# Battery_Charger.net
KiCad netlist of a schematic drawn in EAGLE
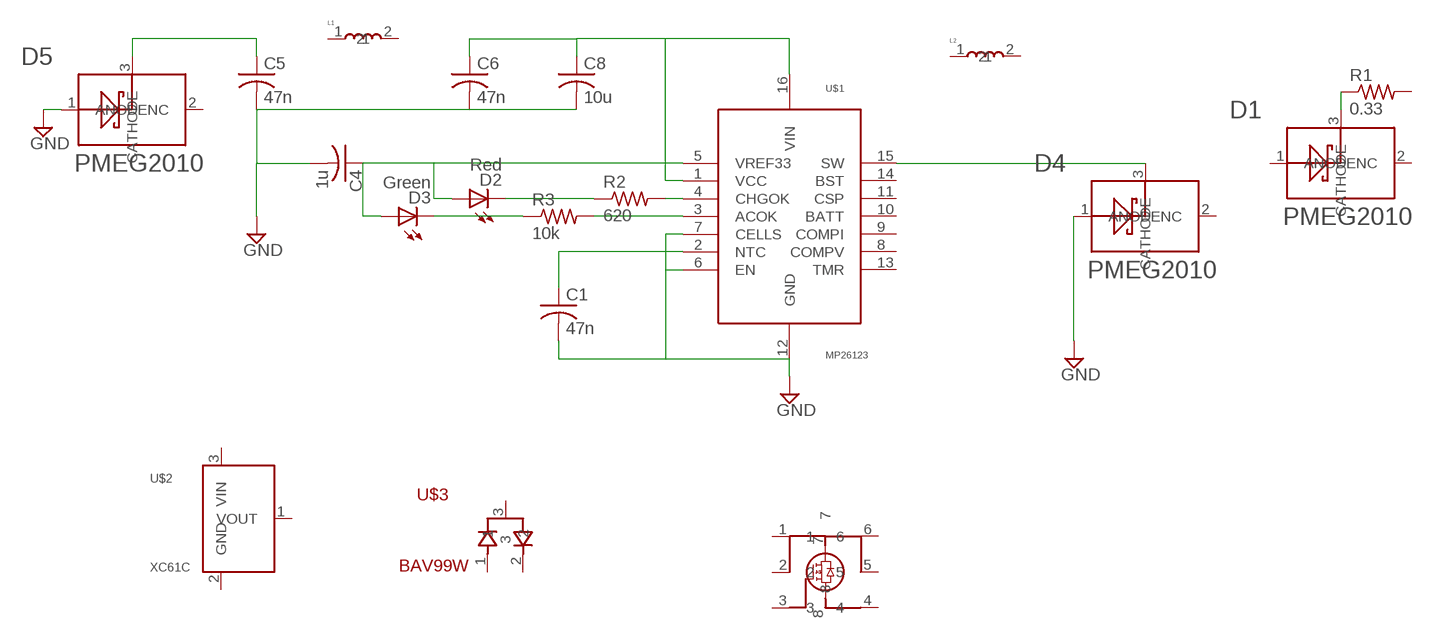
[diagram p0: schematic, sheet 1]

(export (version "E")
  (design (tool "Eeschema 10.0.6"))
  (components
    (comp (ref "C1")
      (value "47n")
      (footprint "eagle-import:C0805")
      (libsource (lib "eagle-import") (part "C-USC0805"))
    )
    (comp (ref "C4")
      (value "1u")
      (footprint "eagle-import:C0805")
      (libsource (lib "eagle-import") (part "C-USC0805"))
    )
    (comp (ref "C5")
      (value "47n")
      (footprint "eagle-import:C0805")
      (libsource (lib "eagle-import") (part "C-USC0805"))
    )
    (comp (ref "C6")
      (value "47n")
      (footprint "eagle-import:C0805")
      (libsource (lib "eagle-import") (part "C-USC0805"))
    )
    (comp (ref "C8")
      (value "10u")
      (footprint "eagle-import:C0805")
      (libsource (lib "eagle-import") (part "C-USC0805"))
    )
    (comp (ref "D1")
      (value "DIODE-PMEG2010")
      (footprint "eagle-import:DIODE-SOT23")
      (libsource (lib "eagle-import") (part "DIODE-PMEG2010"))
    )
    (comp (ref "D2")
      (value "Red")
      (footprint "eagle-import:LED3MM")
      (libsource (lib "eagle-import") (part "LED3MM"))
    )
    (comp (ref "D3")
      (value "Green")
      (footprint "eagle-import:LED3MM")
      (libsource (lib "eagle-import") (part "LED3MM"))
    )
    (comp (ref "D4")
      (value "DIODE-PMEG2010")
      (footprint "eagle-import:DIODE-SOT23")
      (libsource (lib "eagle-import") (part "DIODE-PMEG2010"))
    )
    (comp (ref "D5")
      (value "DIODE-PMEG2010")
      (footprint "eagle-import:DIODE-SOT23")
      (libsource (lib "eagle-import") (part "DIODE-PMEG2010"))
    )
    (comp (ref "L1")
      (value "L-SMD-2")
      (footprint "eagle-import:SMD-2")
      (libsource (lib "eagle-import") (part "L-SMD-2"))
    )
    (comp (ref "L2")
      (value "L-SMD-2")
      (footprint "eagle-import:SMD-2")
      (libsource (lib "eagle-import") (part "L-SMD-2"))
    )
    (comp (ref "Q1")
      (value "MOSFET-IRFHS8242")
      (footprint "eagle-import:PQFN2X2")
      (libsource (lib "eagle-import") (part "MOSFET-IRFHS8242"))
    )
    (comp (ref "R1")
      (value "0.33")
      (footprint "eagle-import:R2512")
      (libsource (lib "eagle-import") (part "R-US_R2512"))
    )
    (comp (ref "R2")
      (value "620")
      (footprint "eagle-import:R0805")
      (libsource (lib "eagle-import") (part "R-US_R0805"))
    )
    (comp (ref "R3")
      (value "10k")
      (footprint "eagle-import:R0805")
      (libsource (lib "eagle-import") (part "R-US_R0805"))
    )
    (comp (ref "U$1")
      (value "IC-MP26123")
      (footprint "eagle-import:QFN16-4MM")
      (libsource (lib "eagle-import") (part "IC-MP26123"))
    )
    (comp (ref "U$2")
      (value "IC-XC61C")
      (footprint "eagle-import:SOT23")
      (libsource (lib "eagle-import") (part "IC-XC61C"))
    )
    (comp (ref "U$3")
      (value "DIODE-BAV99W")
      (footprint "eagle-import:SOT323")
      (libsource (lib "eagle-import") (part "DIODE-BAV99W"))
    )
  )
  (nets
    (net (code "1") (name "/1") (class "Default")
      (node (ref "Q1") (pin "1") (pinfunction "1_1") (pintype "power_in"))
    )
    (net (code "2") (name "/2") (class "Default")
      (node (ref "Q1") (pin "2") (pinfunction "2_2") (pintype "power_in"))
    )
    (net (code "3") (name "/4") (class "Default")
      (node (ref "Q1") (pin "4") (pinfunction "4_4") (pintype "power_in"))
    )
    (net (code "4") (name "/5") (class "Default")
      (node (ref "Q1") (pin "5") (pinfunction "5_5") (pintype "power_in"))
    )
    (net (code "5") (name "/6") (class "Default")
      (node (ref "Q1") (pin "6") (pinfunction "6_6") (pintype "power_in"))
    )
    (net (code "6") (name "/7") (class "Default")
      (node (ref "Q1") (pin "7") (pinfunction "7_7") (pintype "power_in"))
    )
    (net (code "7") (name "/8") (class "Default")
      (node (ref "Q1") (pin "8") (pinfunction "8_8") (pintype "power_in"))
    )
    (net (code "8") (name "GND") (class "Default")
      (node (ref "C1") (pin "2") (pinfunction "2_2") (pintype "passive"))
      (node (ref "C4") (pin "2") (pinfunction "2_2") (pintype "passive"))
      (node (ref "C5") (pin "2") (pinfunction "2_2") (pintype "passive"))
      (node (ref "C6") (pin "2") (pinfunction "2_2") (pintype "passive"))
      (node (ref "C8") (pin "2") (pinfunction "2_2") (pintype "passive"))
      (node (ref "D4") (pin "1") (pinfunction "ANODE_1") (pintype "bidirectional"))
      (node (ref "D5") (pin "1") (pinfunction "ANODE_1") (pintype "bidirectional"))
      (node (ref "U$1") (pin "12") (pinfunction "GND_12") (pintype "bidirectional"))
      (node (ref "U$1") (pin "6") (pinfunction "EN_6") (pintype "bidirectional"))
      (node (ref "U$1") (pin "7") (pinfunction "CELLS_7") (pintype "bidirectional"))
    )
    (net (code "9") (name "Net-(D1-CATHODE)") (class "Default")
      (node (ref "D1") (pin "3") (pinfunction "CATHODE_3") (pintype "bidirectional"))
      (node (ref "R1") (pin "1") (pinfunction "1_1") (pintype "passive"))
    )
    (net (code "10") (name "Net-(D2-C)") (class "Default")
      (node (ref "D2") (pin "K") (pinfunction "C_K") (pintype "passive"))
      (node (ref "R2") (pin "1") (pinfunction "1_1") (pintype "passive"))
    )
    (net (code "11") (name "Net-(D3-C)") (class "Default")
      (node (ref "D3") (pin "K") (pinfunction "C_K") (pintype "passive"))
      (node (ref "R3") (pin "1") (pinfunction "1_1") (pintype "passive"))
    )
    (net (code "12") (name "Net-(D4-CATHODE)") (class "Default")
      (node (ref "D4") (pin "3") (pinfunction "CATHODE_3") (pintype "bidirectional"))
      (node (ref "U$1") (pin "15") (pinfunction "SW_15") (pintype "bidirectional"))
    )
    (net (code "13") (name "Net-(D5-CATHODE)") (class "Default")
      (node (ref "C5") (pin "1") (pinfunction "1_1") (pintype "passive"))
      (node (ref "D5") (pin "3") (pinfunction "CATHODE_3") (pintype "bidirectional"))
    )
    (net (code "14") (name "Net-(U$1-ACOK)") (class "Default")
      (node (ref "R3") (pin "2") (pinfunction "2_2") (pintype "passive"))
      (node (ref "U$1") (pin "3") (pinfunction "ACOK_3") (pintype "bidirectional"))
    )
    (net (code "15") (name "Net-(U$1-CHGOK)") (class "Default")
      (node (ref "R2") (pin "2") (pinfunction "2_2") (pintype "passive"))
      (node (ref "U$1") (pin "4") (pinfunction "CHGOK_4") (pintype "bidirectional"))
    )
    (net (code "16") (name "Net-(U$1-NTC)") (class "Default")
      (node (ref "C1") (pin "1") (pinfunction "1_1") (pintype "passive"))
      (node (ref "U$1") (pin "2") (pinfunction "NTC_2") (pintype "bidirectional"))
    )
    (net (code "17") (name "Net-(U$1-VCC)") (class "Default")
      (node (ref "C6") (pin "1") (pinfunction "1_1") (pintype "passive"))
      (node (ref "C8") (pin "1") (pinfunction "1_1") (pintype "passive"))
      (node (ref "U$1") (pin "1") (pinfunction "VCC_1") (pintype "bidirectional"))
      (node (ref "U$1") (pin "16") (pinfunction "VIN_16") (pintype "bidirectional"))
    )
    (net (code "18") (name "Net-(U$1-VREF33)") (class "Default")
      (node (ref "C4") (pin "1") (pinfunction "1_1") (pintype "passive"))
      (node (ref "D2") (pin "A") (pinfunction "A_A") (pintype "passive"))
      (node (ref "D3") (pin "A") (pinfunction "A_A") (pintype "passive"))
      (node (ref "U$1") (pin "5") (pinfunction "VREF33_5") (pintype "bidirectional"))
    )
    (net (code "19") (name "unconnected-(D1-ANODE-Pad1)") (class "Default")
      (node (ref "D1") (pin "1") (pinfunction "ANODE_1") (pintype "bidirectional"))
    )
    (net (code "20") (name "unconnected-(D1-NC-Pad2)") (class "Default")
      (node (ref "D1") (pin "2") (pinfunction "NC_2") (pintype "bidirectional"))
    )
    (net (code "21") (name "unconnected-(D4-NC-Pad2)") (class "Default")
      (node (ref "D4") (pin "2") (pinfunction "NC_2") (pintype "bidirectional"))
    )
    (net (code "22") (name "unconnected-(D5-NC-Pad2)") (class "Default")
      (node (ref "D5") (pin "2") (pinfunction "NC_2") (pintype "bidirectional"))
    )
    (net (code "23") (name "unconnected-(L1-Pad1)") (class "Default")
      (node (ref "L1") (pin "1") (pinfunction "1_1") (pintype "passive"))
    )
    (net (code "24") (name "unconnected-(L1-Pad2)") (class "Default")
      (node (ref "L1") (pin "2") (pinfunction "2_2") (pintype "passive"))
    )
    (net (code "25") (name "unconnected-(L2-Pad1)") (class "Default")
      (node (ref "L2") (pin "1") (pinfunction "1_1") (pintype "passive"))
    )
    (net (code "26") (name "unconnected-(L2-Pad2)") (class "Default")
      (node (ref "L2") (pin "2") (pinfunction "2_2") (pintype "passive"))
    )
    (net (code "27") (name "unconnected-(Q1-Pad3)") (class "Default")
      (node (ref "Q1") (pin "3") (pinfunction "3_3") (pintype "input"))
    )
    (net (code "28") (name "unconnected-(R1-Pad2)") (class "Default")
      (node (ref "R1") (pin "2") (pinfunction "2_2") (pintype "passive"))
    )
    (net (code "29") (name "unconnected-(U$1-BATT-Pad10)") (class "Default")
      (node (ref "U$1") (pin "10") (pinfunction "BATT_10") (pintype "bidirectional"))
    )
    (net (code "30") (name "unconnected-(U$1-BST-Pad14)") (class "Default")
      (node (ref "U$1") (pin "14") (pinfunction "BST_14") (pintype "bidirectional"))
    )
    (net (code "31") (name "unconnected-(U$1-COMPI-Pad9)") (class "Default")
      (node (ref "U$1") (pin "9") (pinfunction "COMPI_9") (pintype "bidirectional"))
    )
    (net (code "32") (name "unconnected-(U$1-COMPV-Pad8)") (class "Default")
      (node (ref "U$1") (pin "8") (pinfunction "COMPV_8") (pintype "bidirectional"))
    )
    (net (code "33") (name "unconnected-(U$1-CSP-Pad11)") (class "Default")
      (node (ref "U$1") (pin "11") (pinfunction "CSP_11") (pintype "bidirectional"))
    )
    (net (code "34") (name "unconnected-(U$1-TMR-Pad13)") (class "Default")
      (node (ref "U$1") (pin "13") (pinfunction "TMR_13") (pintype "bidirectional"))
    )
    (net (code "35") (name "unconnected-(U$2-GND-Pad2)") (class "Default")
      (node (ref "U$2") (pin "2") (pinfunction "GND_2") (pintype "bidirectional"))
    )
    (net (code "36") (name "unconnected-(U$2-VIN-Pad3)") (class "Default")
      (node (ref "U$2") (pin "3") (pinfunction "VIN_3") (pintype "bidirectional"))
    )
    (net (code "37") (name "unconnected-(U$2-VOUT-Pad1)") (class "Default")
      (node (ref "U$2") (pin "1") (pinfunction "VOUT_1") (pintype "bidirectional"))
    )
    (net (code "38") (name "unconnected-(U$3-Pad1)") (class "Default")
      (node (ref "U$3") (pin "1") (pinfunction "1_1") (pintype "bidirectional"))
    )
    (net (code "39") (name "unconnected-(U$3-Pad2)") (class "Default")
      (node (ref "U$3") (pin "2") (pinfunction "2_2") (pintype "bidirectional"))
    )
    (net (code "40") (name "unconnected-(U$3-Pad3)") (class "Default")
      (node (ref "U$3") (pin "3") (pinfunction "3_3") (pintype "bidirectional"))
    )
  )
)
